# PlusShield.net
KiCad netlist of a schematic drawn in EAGLE
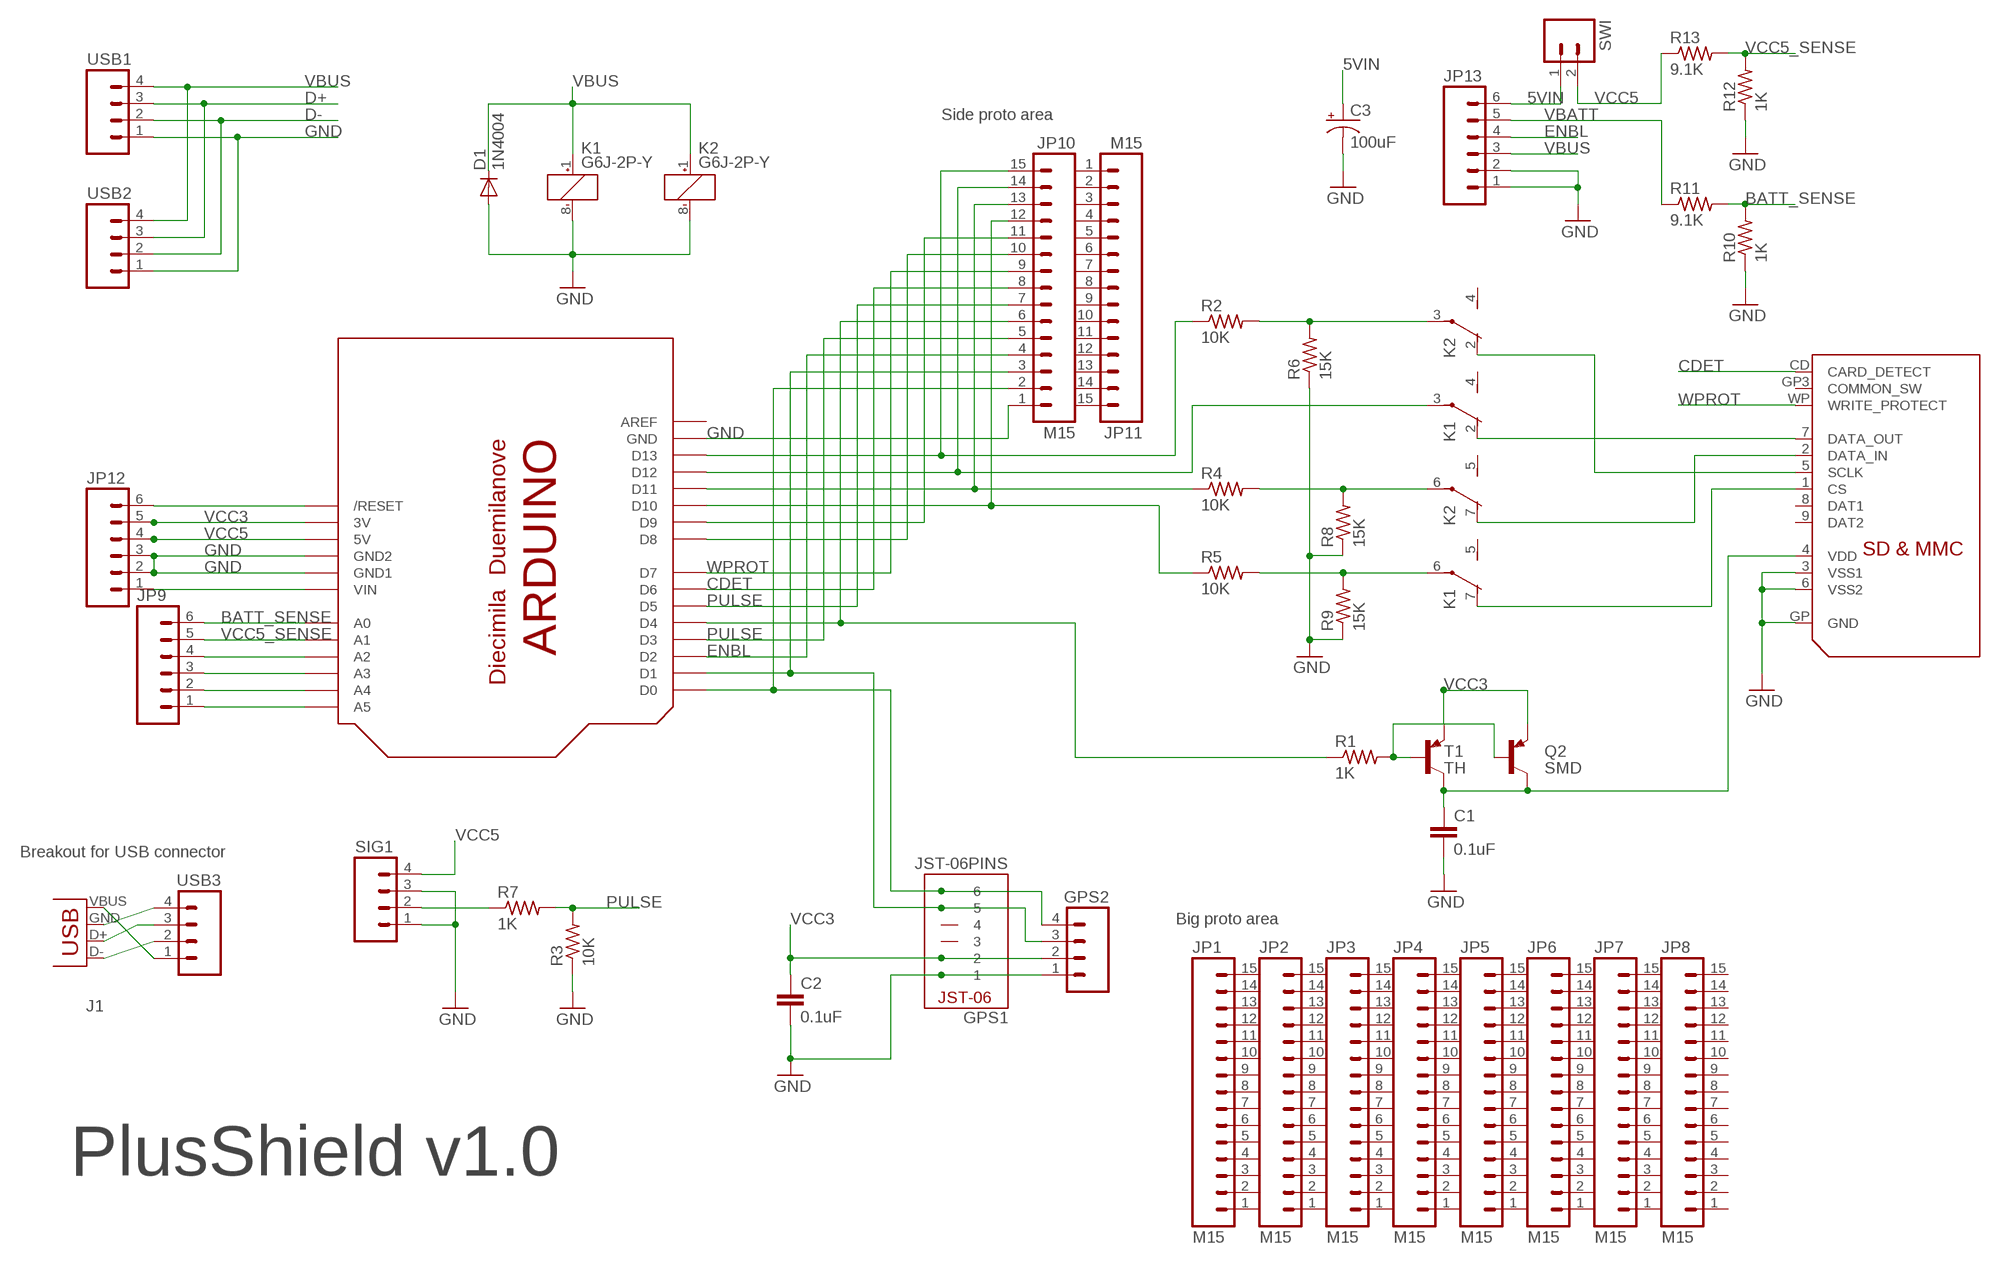
[diagram p0: schematic, sheet 1]

(export (version "E")
  (design (tool "Eeschema 10.0.6"))
  (components
    (comp (ref "C1")
      (value "0.1uF")
      (footprint "eagle-import:CAP-PTH-5MM")
      (libsource (lib "eagle-import") (part "CAPPTH1"))
    )
    (comp (ref "C2")
      (value "0.1uF")
      (footprint "eagle-import:CAP-PTH-5MM")
      (libsource (lib "eagle-import") (part "CAPPTH1"))
    )
    (comp (ref "C3")
      (value "100uF")
      (footprint "eagle-import:EIA7343")
      (libsource (lib "eagle-import") (part "CAP_POL7343"))
    )
    (comp (ref "D1")
      (value "1N4004")
      (footprint "eagle-import:DO41-10")
      (libsource (lib "eagle-import") (part "1N4004"))
    )
    (comp (ref "GPS1")
      (value "JST-06PINS")
      (footprint "eagle-import:JST-SM06B-SRSS-TB")
      (libsource (lib "eagle-import") (part "JST-06PINS"))
    )
    (comp (ref "GPS2")
      (value "M04PTH")
      (footprint "eagle-import:1X04")
      (libsource (lib "eagle-import") (part "M04PTH"))
    )
    (comp (ref "J1")
      (value "USB-A-DIP")
      (footprint "eagle-import:A-DIP")
      (libsource (lib "eagle-import") (part "USB-A-DIP"))
    )
    (comp (ref "JP1")
      (value "M15")
      (footprint "eagle-import:1X15")
      (libsource (lib "eagle-import") (part "M15"))
    )
    (comp (ref "JP2")
      (value "M15")
      (footprint "eagle-import:1X15")
      (libsource (lib "eagle-import") (part "M15"))
    )
    (comp (ref "JP3")
      (value "M15")
      (footprint "eagle-import:1X15")
      (libsource (lib "eagle-import") (part "M15"))
    )
    (comp (ref "JP4")
      (value "M15")
      (footprint "eagle-import:1X15")
      (libsource (lib "eagle-import") (part "M15"))
    )
    (comp (ref "JP5")
      (value "M15")
      (footprint "eagle-import:1X15")
      (libsource (lib "eagle-import") (part "M15"))
    )
    (comp (ref "JP6")
      (value "M15")
      (footprint "eagle-import:1X15")
      (libsource (lib "eagle-import") (part "M15"))
    )
    (comp (ref "JP7")
      (value "M15")
      (footprint "eagle-import:1X15")
      (libsource (lib "eagle-import") (part "M15"))
    )
    (comp (ref "JP8")
      (value "M15")
      (footprint "eagle-import:1X15")
      (libsource (lib "eagle-import") (part "M15"))
    )
    (comp (ref "JP9")
      (value "M06SIP")
      (footprint "eagle-import:1X06")
      (libsource (lib "eagle-import") (part "M06SIP"))
    )
    (comp (ref "JP10")
      (value "M15")
      (footprint "eagle-import:1X15")
      (libsource (lib "eagle-import") (part "M15"))
    )
    (comp (ref "JP11")
      (value "M15")
      (footprint "eagle-import:1X15")
      (libsource (lib "eagle-import") (part "M15"))
    )
    (comp (ref "JP12")
      (value "M06SIP")
      (footprint "eagle-import:1X06")
      (libsource (lib "eagle-import") (part "M06SIP"))
    )
    (comp (ref "JP13")
      (value "M06SIP")
      (footprint "eagle-import:1X06")
      (libsource (lib "eagle-import") (part "M06SIP"))
    )
    (comp (ref "K1")
      (value "G6J-2P-Y")
      (footprint "eagle-import:G6J-2P-Y")
      (fields (field (name "MF") "OMRON COMPONENTS USA") (field (name "MPN") "G6J-2P-Y-DC12"))
      (libsource (lib "eagle-import") (part "G6J-2?-YP"))
    )
    (comp (ref "K2")
      (value "G6J-2P-Y")
      (footprint "eagle-import:G6J-2P-Y")
      (fields (field (name "MF") "OMRON COMPONENTS USA") (field (name "MPN") "G6J-2P-Y-DC12"))
      (libsource (lib "eagle-import") (part "G6J-2?-YP"))
    )
    (comp (ref "Q2")
      (value "SMD")
      (footprint "eagle-import:SOT23")
      (libsource (lib "eagle-import") (part "-?SOT23MMBTA56"))
    )
    (comp (ref "R1")
      (value "1K")
      (footprint "eagle-import:0207_10")
      (libsource (lib "eagle-import") (part "R-US_0207/10"))
    )
    (comp (ref "R2")
      (value "10K")
      (footprint "eagle-import:0207_10")
      (libsource (lib "eagle-import") (part "R-US_0207/10"))
    )
    (comp (ref "R3")
      (value "10K")
      (footprint "eagle-import:0207_10")
      (libsource (lib "eagle-import") (part "R-US_0207/10"))
    )
    (comp (ref "R4")
      (value "10K")
      (footprint "eagle-import:0207_10")
      (libsource (lib "eagle-import") (part "R-US_0207/10"))
    )
    (comp (ref "R5")
      (value "10K")
      (footprint "eagle-import:0207_10")
      (libsource (lib "eagle-import") (part "R-US_0207/10"))
    )
    (comp (ref "R6")
      (value "15K")
      (footprint "eagle-import:0207_10")
      (libsource (lib "eagle-import") (part "R-US_0207/10"))
    )
    (comp (ref "R7")
      (value "1K")
      (footprint "eagle-import:0207_10")
      (libsource (lib "eagle-import") (part "R-US_0207/10"))
    )
    (comp (ref "R8")
      (value "15K")
      (footprint "eagle-import:0207_10")
      (libsource (lib "eagle-import") (part "R-US_0207/10"))
    )
    (comp (ref "R9")
      (value "15K")
      (footprint "eagle-import:0207_10")
      (libsource (lib "eagle-import") (part "R-US_0207/10"))
    )
    (comp (ref "R10")
      (value "1K")
      (footprint "eagle-import:0207_10")
      (libsource (lib "eagle-import") (part "R-US_0207/10"))
    )
    (comp (ref "R11")
      (value "9.1K")
      (footprint "eagle-import:0207_10")
      (libsource (lib "eagle-import") (part "R-US_0207/10"))
    )
    (comp (ref "R12")
      (value "1K")
      (footprint "eagle-import:0207_10")
      (libsource (lib "eagle-import") (part "R-US_0207/10"))
    )
    (comp (ref "R13")
      (value "9.1K")
      (footprint "eagle-import:0207_10")
      (libsource (lib "eagle-import") (part "R-US_0207/10"))
    )
    (comp (ref "SIG1")
      (value "M04PTH")
      (footprint "eagle-import:1X04")
      (libsource (lib "eagle-import") (part "M04PTH"))
    )
    (comp (ref "SWI")
      (value "M02PTH")
      (footprint "eagle-import:1X02")
      (libsource (lib "eagle-import") (part "M02PTH"))
    )
    (comp (ref "T1")
      (value "TH")
      (footprint "eagle-import:TO92-CBE")
      (libsource (lib "eagle-import") (part "-?TO92MPSA56"))
    )
    (comp (ref "U$1")
      (value "SDMMC06132")
      (footprint "eagle-import:06132")
      (libsource (lib "eagle-import") (part "SDMMC06132"))
    )
    (comp (ref "U$2")
      (value "ARDUINOSHIELD-NOHOLE")
      (footprint "eagle-import:ARDUINO-NOHOLE")
      (libsource (lib "eagle-import") (part "ARDUINOSHIELD-NOHOLE"))
    )
    (comp (ref "USB1")
      (value "M04PTH")
      (footprint "eagle-import:1X04")
      (libsource (lib "eagle-import") (part "M04PTH"))
    )
    (comp (ref "USB2")
      (value "M04PTH")
      (footprint "eagle-import:1X04")
      (libsource (lib "eagle-import") (part "M04PTH"))
    )
    (comp (ref "USB3")
      (value "M04PTH")
      (footprint "eagle-import:1X04")
      (libsource (lib "eagle-import") (part "M04PTH"))
    )
  )
  (nets
    (net (code "1") (name "/5VIN") (class "Default")
      (node (ref "C3") (pin "A") (pinfunction "+_A") (pintype "passive"))
      (node (ref "JP13") (pin "6") (pinfunction "6_6") (pintype "passive"))
      (node (ref "SWI") (pin "1") (pinfunction "1_1") (pintype "passive"))
    )
    (net (code "2") (name "/BATT_SENSE") (class "Default")
      (node (ref "JP9") (pin "6") (pinfunction "6_6") (pintype "passive"))
      (node (ref "R10") (pin "2") (pinfunction "2_2") (pintype "passive"))
      (node (ref "R11") (pin "2") (pinfunction "2_2") (pintype "passive"))
      (node (ref "U$2") (pin "A0") (pinfunction "A0_A0") (pintype "bidirectional"))
    )
    (net (code "3") (name "/CDET") (class "Default")
      (node (ref "JP10") (pin "8") (pinfunction "8_8") (pintype "passive"))
      (node (ref "U$1") (pin "CD") (pinfunction "CARD_DETECT_CD") (pintype "passive"))
      (node (ref "U$2") (pin "D6") (pinfunction "D6_D6") (pintype "bidirectional"))
    )
    (net (code "4") (name "/D+") (class "Default")
      (node (ref "USB1") (pin "3") (pinfunction "3_3") (pintype "passive"))
      (node (ref "USB2") (pin "3") (pinfunction "3_3") (pintype "passive"))
    )
    (net (code "5") (name "/D-") (class "Default")
      (node (ref "USB1") (pin "2") (pinfunction "2_2") (pintype "passive"))
      (node (ref "USB2") (pin "2") (pinfunction "2_2") (pintype "passive"))
    )
    (net (code "6") (name "/ENBL") (class "Default")
      (node (ref "JP10") (pin "4") (pinfunction "4_4") (pintype "passive"))
      (node (ref "JP13") (pin "4") (pinfunction "4_4") (pintype "passive"))
      (node (ref "U$2") (pin "D2") (pinfunction "D2_D2") (pintype "bidirectional"))
    )
    (net (code "7") (name "/PULSE") (class "Default")
      (node (ref "JP10") (pin "5") (pinfunction "5_5") (pintype "passive"))
      (node (ref "JP10") (pin "7") (pinfunction "7_7") (pintype "passive"))
      (node (ref "R3") (pin "2") (pinfunction "2_2") (pintype "passive"))
      (node (ref "R7") (pin "2") (pinfunction "2_2") (pintype "passive"))
      (node (ref "U$2") (pin "D3") (pinfunction "D3_D3") (pintype "bidirectional"))
      (node (ref "U$2") (pin "D5") (pinfunction "D5_D5") (pintype "bidirectional"))
    )
    (net (code "8") (name "/VBATT") (class "Default")
      (node (ref "JP13") (pin "5") (pinfunction "5_5") (pintype "passive"))
      (node (ref "R11") (pin "1") (pinfunction "1_1") (pintype "passive"))
    )
    (net (code "9") (name "/VBUS") (class "Default")
      (node (ref "D1") (pin "C") (pinfunction "C_C") (pintype "passive"))
      (node (ref "JP13") (pin "3") (pinfunction "3_3") (pintype "passive"))
      (node (ref "K1") (pin "1") (pinfunction "+_1") (pintype "passive"))
      (node (ref "K2") (pin "1") (pinfunction "+_1") (pintype "passive"))
      (node (ref "USB1") (pin "4") (pinfunction "4_4") (pintype "passive"))
      (node (ref "USB2") (pin "4") (pinfunction "4_4") (pintype "passive"))
    )
    (net (code "10") (name "/VCC3") (class "Default")
      (node (ref "C2") (pin "1") (pinfunction "1_1") (pintype "passive"))
      (node (ref "GPS1") (pin "2") (pinfunction "2_2") (pintype "bidirectional"))
      (node (ref "GPS2") (pin "2") (pinfunction "2_2") (pintype "passive"))
      (node (ref "JP12") (pin "5") (pinfunction "5_5") (pintype "passive"))
      (node (ref "Q2") (pin "2") (pinfunction "E_2") (pintype "passive"))
      (node (ref "T1") (pin "E") (pinfunction "E_E") (pintype "passive"))
      (node (ref "U$2") (pin "3V") (pinfunction "3V_3V") (pintype "power_in"))
    )
    (net (code "11") (name "/VCC5") (class "Default")
      (node (ref "JP12") (pin "4") (pinfunction "4_4") (pintype "passive"))
      (node (ref "R13") (pin "1") (pinfunction "1_1") (pintype "passive"))
      (node (ref "SIG1") (pin "4") (pinfunction "4_4") (pintype "passive"))
      (node (ref "SWI") (pin "2") (pinfunction "2_2") (pintype "passive"))
      (node (ref "U$2") (pin "5V") (pinfunction "5V_5V") (pintype "power_in"))
    )
    (net (code "12") (name "/VCC5_SENSE") (class "Default")
      (node (ref "JP9") (pin "5") (pinfunction "5_5") (pintype "passive"))
      (node (ref "R12") (pin "2") (pinfunction "2_2") (pintype "passive"))
      (node (ref "R13") (pin "2") (pinfunction "2_2") (pintype "passive"))
      (node (ref "U$2") (pin "A1") (pinfunction "A1_A1") (pintype "bidirectional"))
    )
    (net (code "13") (name "/WPROT") (class "Default")
      (node (ref "JP10") (pin "9") (pinfunction "9_9") (pintype "passive"))
      (node (ref "U$1") (pin "WP") (pinfunction "WRITE_PROTECT_WP") (pintype "passive"))
      (node (ref "U$2") (pin "D7") (pinfunction "D7_D7") (pintype "bidirectional"))
    )
    (net (code "14") (name "GND") (class "Default")
      (node (ref "C1") (pin "2") (pinfunction "2_2") (pintype "passive"))
      (node (ref "C2") (pin "2") (pinfunction "2_2") (pintype "passive"))
      (node (ref "C3") (pin "C") (pinfunction "-_C") (pintype "passive"))
      (node (ref "D1") (pin "A") (pinfunction "A_A") (pintype "passive"))
      (node (ref "GPS1") (pin "1") (pinfunction "1_1") (pintype "bidirectional"))
      (node (ref "GPS2") (pin "1") (pinfunction "1_1") (pintype "passive"))
      (node (ref "JP10") (pin "1") (pinfunction "1_1") (pintype "passive"))
      (node (ref "JP12") (pin "2") (pinfunction "2_2") (pintype "passive"))
      (node (ref "JP12") (pin "3") (pinfunction "3_3") (pintype "passive"))
      (node (ref "JP13") (pin "1") (pinfunction "1_1") (pintype "passive"))
      (node (ref "JP13") (pin "2") (pinfunction "2_2") (pintype "passive"))
      (node (ref "K1") (pin "8") (pinfunction "-_8") (pintype "passive"))
      (node (ref "K2") (pin "8") (pinfunction "-_8") (pintype "passive"))
      (node (ref "R10") (pin "1") (pinfunction "1_1") (pintype "passive"))
      (node (ref "R12") (pin "1") (pinfunction "1_1") (pintype "passive"))
      (node (ref "R3") (pin "1") (pinfunction "1_1") (pintype "passive"))
      (node (ref "R6") (pin "1") (pinfunction "1_1") (pintype "passive"))
      (node (ref "R8") (pin "1") (pinfunction "1_1") (pintype "passive"))
      (node (ref "R9") (pin "1") (pinfunction "1_1") (pintype "passive"))
      (node (ref "SIG1") (pin "1") (pinfunction "1_1") (pintype "passive"))
      (node (ref "SIG1") (pin "3") (pinfunction "3_3") (pintype "passive"))
      (node (ref "U$1") (pin "3") (pinfunction "VSS1_3") (pintype "power_in"))
      (node (ref "U$1") (pin "6") (pinfunction "VSS2_6") (pintype "power_in"))
      (node (ref "U$1") (pin "GP") (pinfunction "GND_GP") (pintype "power_in"))
      (node (ref "U$2") (pin "GND") (pinfunction "GND_GND") (pintype "power_in"))
      (node (ref "U$2") (pin "GND1") (pinfunction "GND1_GND1") (pintype "power_in"))
      (node (ref "U$2") (pin "GND2") (pinfunction "GND2_GND2") (pintype "power_in"))
      (node (ref "USB1") (pin "1") (pinfunction "1_1") (pintype "passive"))
      (node (ref "USB2") (pin "1") (pinfunction "1_1") (pintype "passive"))
    )
    (net (code "15") (name "Net-(GPS1-Pad5)") (class "Default")
      (node (ref "GPS1") (pin "5") (pinfunction "5_5") (pintype "bidirectional"))
      (node (ref "GPS2") (pin "3") (pinfunction "3_3") (pintype "passive"))
      (node (ref "JP10") (pin "3") (pinfunction "3_3") (pintype "passive"))
      (node (ref "U$2") (pin "D1") (pinfunction "D1_D1") (pintype "bidirectional"))
    )
    (net (code "16") (name "Net-(GPS1-Pad6)") (class "Default")
      (node (ref "GPS1") (pin "6") (pinfunction "6_6") (pintype "bidirectional"))
      (node (ref "GPS2") (pin "4") (pinfunction "4_4") (pintype "passive"))
      (node (ref "JP10") (pin "2") (pinfunction "2_2") (pintype "passive"))
      (node (ref "U$2") (pin "D0") (pinfunction "D0_D0") (pintype "bidirectional"))
    )
    (net (code "17") (name "Net-(J1-D+)") (class "Default")
      (node (ref "J1") (pin "D-") (pinfunction "D+_D-") (pintype "bidirectional"))
      (node (ref "USB3") (pin "2") (pinfunction "2_2") (pintype "passive"))
    )
    (net (code "18") (name "Net-(J1-D-)") (class "Default")
      (node (ref "J1") (pin "D+") (pinfunction "D-_D+") (pintype "bidirectional"))
      (node (ref "USB3") (pin "3") (pinfunction "3_3") (pintype "passive"))
    )
    (net (code "19") (name "Net-(J1-GND)") (class "Default")
      (node (ref "J1") (pin "VBUS") (pinfunction "GND_VBUS") (pintype "bidirectional"))
      (node (ref "USB3") (pin "1") (pinfunction "1_1") (pintype "passive"))
    )
    (net (code "20") (name "Net-(J1-VBUS)") (class "Default")
      (node (ref "J1") (pin "GND") (pinfunction "VBUS_GND") (pintype "bidirectional"))
      (node (ref "USB3") (pin "4") (pinfunction "4_4") (pintype "passive"))
    )
    (net (code "21") (name "Net-(JP9-Pad1)") (class "Default")
      (node (ref "JP9") (pin "1") (pinfunction "1_1") (pintype "passive"))
      (node (ref "U$2") (pin "A5") (pinfunction "A5_A5") (pintype "bidirectional"))
    )
    (net (code "22") (name "Net-(JP9-Pad2)") (class "Default")
      (node (ref "JP9") (pin "2") (pinfunction "2_2") (pintype "passive"))
      (node (ref "U$2") (pin "A4") (pinfunction "A4_A4") (pintype "bidirectional"))
    )
    (net (code "23") (name "Net-(JP9-Pad3)") (class "Default")
      (node (ref "JP9") (pin "3") (pinfunction "3_3") (pintype "passive"))
      (node (ref "U$2") (pin "A3") (pinfunction "A3_A3") (pintype "bidirectional"))
    )
    (net (code "24") (name "Net-(JP9-Pad4)") (class "Default")
      (node (ref "JP9") (pin "4") (pinfunction "4_4") (pintype "passive"))
      (node (ref "U$2") (pin "A2") (pinfunction "A2_A2") (pintype "bidirectional"))
    )
    (net (code "25") (name "Net-(JP10-Pad6)") (class "Default")
      (node (ref "JP10") (pin "6") (pinfunction "6_6") (pintype "passive"))
      (node (ref "R1") (pin "1") (pinfunction "1_1") (pintype "passive"))
      (node (ref "U$2") (pin "D4") (pinfunction "D4_D4") (pintype "bidirectional"))
    )
    (net (code "26") (name "Net-(JP10-Pad10)") (class "Default")
      (node (ref "JP10") (pin "10") (pinfunction "10_10") (pintype "passive"))
      (node (ref "U$2") (pin "D8") (pinfunction "D8_D8") (pintype "bidirectional"))
    )
    (net (code "27") (name "Net-(JP10-Pad11)") (class "Default")
      (node (ref "JP10") (pin "11") (pinfunction "11_11") (pintype "passive"))
      (node (ref "U$2") (pin "D9") (pinfunction "D9_D9") (pintype "bidirectional"))
    )
    (net (code "28") (name "Net-(JP10-Pad12)") (class "Default")
      (node (ref "JP10") (pin "12") (pinfunction "12_12") (pintype "passive"))
      (node (ref "R5") (pin "1") (pinfunction "1_1") (pintype "passive"))
      (node (ref "U$2") (pin "D10") (pinfunction "D10_D10") (pintype "bidirectional"))
    )
    (net (code "29") (name "Net-(JP10-Pad13)") (class "Default")
      (node (ref "JP10") (pin "13") (pinfunction "13_13") (pintype "passive"))
      (node (ref "R4") (pin "1") (pinfunction "1_1") (pintype "passive"))
      (node (ref "U$2") (pin "D11") (pinfunction "D11_D11") (pintype "bidirectional"))
    )
    (net (code "30") (name "Net-(JP10-Pad15)") (class "Default")
      (node (ref "JP10") (pin "15") (pinfunction "15_15") (pintype "passive"))
      (node (ref "R2") (pin "1") (pinfunction "1_1") (pintype "passive"))
      (node (ref "U$2") (pin "D13") (pinfunction "D13_D13") (pintype "bidirectional"))
    )
    (net (code "31") (name "Net-(JP12-Pad1)") (class "Default")
      (node (ref "JP12") (pin "1") (pinfunction "1_1") (pintype "passive"))
      (node (ref "U$2") (pin "VIN") (pinfunction "VIN_VIN") (pintype "power_in"))
    )
    (net (code "32") (name "Net-(K1B-O)") (class "Default")
      (node (ref "K1") (pin "2") (pinfunction "O_2") (pintype "passive"))
      (node (ref "U$1") (pin "7") (pinfunction "DATA_OUT_7") (pintype "output"))
    )
    (net (code "33") (name "Net-(K1B-P)") (class "Default")
      (node (ref "JP10") (pin "14") (pinfunction "14_14") (pintype "passive"))
      (node (ref "K1") (pin "3") (pinfunction "P_3") (pintype "passive"))
      (node (ref "U$2") (pin "D12") (pinfunction "D12_D12") (pintype "bidirectional"))
    )
    (net (code "34") (name "Net-(K1C-O)") (class "Default")
      (node (ref "K1") (pin "7") (pinfunction "O_7") (pintype "passive"))
      (node (ref "U$1") (pin "1") (pinfunction "CS_1") (pintype "input"))
    )
    (net (code "35") (name "Net-(K1C-P)") (class "Default")
      (node (ref "K1") (pin "6") (pinfunction "P_6") (pintype "passive"))
      (node (ref "R5") (pin "2") (pinfunction "2_2") (pintype "passive"))
      (node (ref "R9") (pin "2") (pinfunction "2_2") (pintype "passive"))
    )
    (net (code "36") (name "Net-(K2B-O)") (class "Default")
      (node (ref "K2") (pin "2") (pinfunction "O_2") (pintype "passive"))
      (node (ref "U$1") (pin "5") (pinfunction "SCLK_5") (pintype "input"))
    )
    (net (code "37") (name "Net-(K2B-P)") (class "Default")
      (node (ref "K2") (pin "3") (pinfunction "P_3") (pintype "passive"))
      (node (ref "R2") (pin "2") (pinfunction "2_2") (pintype "passive"))
      (node (ref "R6") (pin "2") (pinfunction "2_2") (pintype "passive"))
    )
    (net (code "38") (name "Net-(K2C-O)") (class "Default")
      (node (ref "K2") (pin "7") (pinfunction "O_7") (pintype "passive"))
      (node (ref "U$1") (pin "2") (pinfunction "DATA_IN_2") (pintype "input"))
    )
    (net (code "39") (name "Net-(K2C-P)") (class "Default")
      (node (ref "K2") (pin "6") (pinfunction "P_6") (pintype "passive"))
      (node (ref "R4") (pin "2") (pinfunction "2_2") (pintype "passive"))
      (node (ref "R8") (pin "2") (pinfunction "2_2") (pintype "passive"))
    )
    (net (code "40") (name "Net-(Q2-B)") (class "Default")
      (node (ref "Q2") (pin "1") (pinfunction "B_1") (pintype "passive"))
      (node (ref "R1") (pin "2") (pinfunction "2_2") (pintype "passive"))
      (node (ref "T1") (pin "B") (pinfunction "B_B") (pintype "passive"))
    )
    (net (code "41") (name "Net-(Q2-C)") (class "Default")
      (node (ref "C1") (pin "1") (pinfunction "1_1") (pintype "passive"))
      (node (ref "Q2") (pin "3") (pinfunction "C_3") (pintype "passive"))
      (node (ref "T1") (pin "C") (pinfunction "C_C") (pintype "passive"))
      (node (ref "U$1") (pin "4") (pinfunction "VDD_4") (pintype "power_in"))
    )
    (net (code "42") (name "Net-(R7-Pad1)") (class "Default")
      (node (ref "R7") (pin "1") (pinfunction "1_1") (pintype "passive"))
      (node (ref "SIG1") (pin "2") (pinfunction "2_2") (pintype "passive"))
    )
    (net (code "43") (name "Net-(U$2-{slash}RESET)") (class "Default")
      (node (ref "JP12") (pin "6") (pinfunction "6_6") (pintype "passive"))
      (node (ref "U$2") (pin "RESET") (pinfunction "/RESET_RESET") (pintype "bidirectional"))
    )
    (net (code "44") (name "unconnected-(GPS1-Pad3)") (class "Default")
      (node (ref "GPS1") (pin "3") (pinfunction "3_3") (pintype "bidirectional"))
    )
    (net (code "45") (name "unconnected-(GPS1-Pad4)") (class "Default")
      (node (ref "GPS1") (pin "4") (pinfunction "4_4") (pintype "bidirectional"))
    )
    (net (code "46") (name "unconnected-(JP1-Pad1)") (class "Default")
      (node (ref "JP1") (pin "1") (pinfunction "1_1") (pintype "passive"))
    )
    (net (code "47") (name "unconnected-(JP1-Pad2)") (class "Default")
      (node (ref "JP1") (pin "2") (pinfunction "2_2") (pintype "passive"))
    )
    (net (code "48") (name "unconnected-(JP1-Pad3)") (class "Default")
      (node (ref "JP1") (pin "3") (pinfunction "3_3") (pintype "passive"))
    )
    (net (code "49") (name "unconnected-(JP1-Pad4)") (class "Default")
      (node (ref "JP1") (pin "4") (pinfunction "4_4") (pintype "passive"))
    )
    (net (code "50") (name "unconnected-(JP1-Pad5)") (class "Default")
      (node (ref "JP1") (pin "5") (pinfunction "5_5") (pintype "passive"))
    )
    (net (code "51") (name "unconnected-(JP1-Pad6)") (class "Default")
      (node (ref "JP1") (pin "6") (pinfunction "6_6") (pintype "passive"))
    )
    (net (code "52") (name "unconnected-(JP1-Pad7)") (class "Default")
      (node (ref "JP1") (pin "7") (pinfunction "7_7") (pintype "passive"))
    )
    (net (code "53") (name "unconnected-(JP1-Pad8)") (class "Default")
      (node (ref "JP1") (pin "8") (pinfunction "8_8") (pintype "passive"))
    )
    (net (code "54") (name "unconnected-(JP1-Pad9)") (class "Default")
      (node (ref "JP1") (pin "9") (pinfunction "9_9") (pintype "passive"))
    )
    (net (code "55") (name "unconnected-(JP1-Pad10)") (class "Default")
      (node (ref "JP1") (pin "10") (pinfunction "10_10") (pintype "passive"))
    )
    (net (code "56") (name "unconnected-(JP1-Pad11)") (class "Default")
      (node (ref "JP1") (pin "11") (pinfunction "11_11") (pintype "passive"))
    )
    (net (code "57") (name "unconnected-(JP1-Pad12)") (class "Default")
      (node (ref "JP1") (pin "12") (pinfunction "12_12") (pintype "passive"))
    )
    (net (code "58") (name "unconnected-(JP1-Pad13)") (class "Default")
      (node (ref "JP1") (pin "13") (pinfunction "13_13") (pintype "passive"))
    )
    (net (code "59") (name "unconnected-(JP1-Pad14)") (class "Default")
      (node (ref "JP1") (pin "14") (pinfunction "14_14") (pintype "passive"))
    )
    (net (code "60") (name "unconnected-(JP1-Pad15)") (class "Default")
      (node (ref "JP1") (pin "15") (pinfunction "15_15") (pintype "passive"))
    )
    (net (code "61") (name "unconnected-(JP2-Pad1)") (class "Default")
      (node (ref "JP2") (pin "1") (pinfunction "1_1") (pintype "passive"))
    )
    (net (code "62") (name "unconnected-(JP2-Pad2)") (class "Default")
      (node (ref "JP2") (pin "2") (pinfunction "2_2") (pintype "passive"))
    )
    (net (code "63") (name "unconnected-(JP2-Pad3)") (class "Default")
      (node (ref "JP2") (pin "3") (pinfunction "3_3") (pintype "passive"))
    )
    (net (code "64") (name "unconnected-(JP2-Pad4)") (class "Default")
      (node (ref "JP2") (pin "4") (pinfunction "4_4") (pintype "passive"))
    )
    (net (code "65") (name "unconnected-(JP2-Pad5)") (class "Default")
      (node (ref "JP2") (pin "5") (pinfunction "5_5") (pintype "passive"))
    )
    (net (code "66") (name "unconnected-(JP2-Pad6)") (class "Default")
      (node (ref "JP2") (pin "6") (pinfunction "6_6") (pintype "passive"))
    )
    (net (code "67") (name "unconnected-(JP2-Pad7)") (class "Default")
      (node (ref "JP2") (pin "7") (pinfunction "7_7") (pintype "passive"))
    )
    (net (code "68") (name "unconnected-(JP2-Pad8)") (class "Default")
      (node (ref "JP2") (pin "8") (pinfunction "8_8") (pintype "passive"))
    )
    (net (code "69") (name "unconnected-(JP2-Pad9)") (class "Default")
      (node (ref "JP2") (pin "9") (pinfunction "9_9") (pintype "passive"))
    )
    (net (code "70") (name "unconnected-(JP2-Pad10)") (class "Default")
      (node (ref "JP2") (pin "10") (pinfunction "10_10") (pintype "passive"))
    )
    (net (code "71") (name "unconnected-(JP2-Pad11)") (class "Default")
      (node (ref "JP2") (pin "11") (pinfunction "11_11") (pintype "passive"))
    )
    (net (code "72") (name "unconnected-(JP2-Pad12)") (class "Default")
      (node (ref "JP2") (pin "12") (pinfunction "12_12") (pintype "passive"))
    )
    (net (code "73") (name "unconnected-(JP2-Pad13)") (class "Default")
      (node (ref "JP2") (pin "13") (pinfunction "13_13") (pintype "passive"))
    )
    (net (code "74") (name "unconnected-(JP2-Pad14)") (class "Default")
      (node (ref "JP2") (pin "14") (pinfunction "14_14") (pintype "passive"))
    )
    (net (code "75") (name "unconnected-(JP2-Pad15)") (class "Default")
      (node (ref "JP2") (pin "15") (pinfunction "15_15") (pintype "passive"))
    )
    (net (code "76") (name "unconnected-(JP3-Pad1)") (class "Default")
      (node (ref "JP3") (pin "1") (pinfunction "1_1") (pintype "passive"))
    )
    (net (code "77") (name "unconnected-(JP3-Pad2)") (class "Default")
      (node (ref "JP3") (pin "2") (pinfunction "2_2") (pintype "passive"))
    )
    (net (code "78") (name "unconnected-(JP3-Pad3)") (class "Default")
      (node (ref "JP3") (pin "3") (pinfunction "3_3") (pintype "passive"))
    )
    (net (code "79") (name "unconnected-(JP3-Pad4)") (class "Default")
      (node (ref "JP3") (pin "4") (pinfunction "4_4") (pintype "passive"))
    )
    (net (code "80") (name "unconnected-(JP3-Pad5)") (class "Default")
      (node (ref "JP3") (pin "5") (pinfunction "5_5") (pintype "passive"))
    )
    (net (code "81") (name "unconnected-(JP3-Pad6)") (class "Default")
      (node (ref "JP3") (pin "6") (pinfunction "6_6") (pintype "passive"))
    )
    (net (code "82") (name "unconnected-(JP3-Pad7)") (class "Default")
      (node (ref "JP3") (pin "7") (pinfunction "7_7") (pintype "passive"))
    )
    (net (code "83") (name "unconnected-(JP3-Pad8)") (class "Default")
      (node (ref "JP3") (pin "8") (pinfunction "8_8") (pintype "passive"))
    )
    (net (code "84") (name "unconnected-(JP3-Pad9)") (class "Default")
      (node (ref "JP3") (pin "9") (pinfunction "9_9") (pintype "passive"))
    )
    (net (code "85") (name "unconnected-(JP3-Pad10)") (class "Default")
      (node (ref "JP3") (pin "10") (pinfunction "10_10") (pintype "passive"))
    )
    (net (code "86") (name "unconnected-(JP3-Pad11)") (class "Default")
      (node (ref "JP3") (pin "11") (pinfunction "11_11") (pintype "passive"))
    )
    (net (code "87") (name "unconnected-(JP3-Pad12)") (class "Default")
      (node (ref "JP3") (pin "12") (pinfunction "12_12") (pintype "passive"))
    )
    (net (code "88") (name "unconnected-(JP3-Pad13)") (class "Default")
      (node (ref "JP3") (pin "13") (pinfunction "13_13") (pintype "passive"))
    )
    (net (code "89") (name "unconnected-(JP3-Pad14)") (class "Default")
      (node (ref "JP3") (pin "14") (pinfunction "14_14") (pintype "passive"))
    )
    (net (code "90") (name "unconnected-(JP3-Pad15)") (class "Default")
      (node (ref "JP3") (pin "15") (pinfunction "15_15") (pintype "passive"))
    )
    (net (code "91") (name "unconnected-(JP4-Pad1)") (class "Default")
      (node (ref "JP4") (pin "1") (pinfunction "1_1") (pintype "passive"))
    )
    (net (code "92") (name "unconnected-(JP4-Pad2)") (class "Default")
      (node (ref "JP4") (pin "2") (pinfunction "2_2") (pintype "passive"))
    )
    (net (code "93") (name "unconnected-(JP4-Pad3)") (class "Default")
      (node (ref "JP4") (pin "3") (pinfunction "3_3") (pintype "passive"))
    )
    (net (code "94") (name "unconnected-(JP4-Pad4)") (class "Default")
      (node (ref "JP4") (pin "4") (pinfunction "4_4") (pintype "passive"))
    )
    (net (code "95") (name "unconnected-(JP4-Pad5)") (class "Default")
      (node (ref "JP4") (pin "5") (pinfunction "5_5") (pintype "passive"))
    )
    (net (code "96") (name "unconnected-(JP4-Pad6)") (class "Default")
      (node (ref "JP4") (pin "6") (pinfunction "6_6") (pintype "passive"))
    )
    (net (code "97") (name "unconnected-(JP4-Pad7)") (class "Default")
      (node (ref "JP4") (pin "7") (pinfunction "7_7") (pintype "passive"))
    )
    (net (code "98") (name "unconnected-(JP4-Pad8)") (class "Default")
      (node (ref "JP4") (pin "8") (pinfunction "8_8") (pintype "passive"))
    )
    (net (code "99") (name "unconnected-(JP4-Pad9)") (class "Default")
      (node (ref "JP4") (pin "9") (pinfunction "9_9") (pintype "passive"))
    )
    (net (code "100") (name "unconnected-(JP4-Pad10)") (class "Default")
      (node (ref "JP4") (pin "10") (pinfunction "10_10") (pintype "passive"))
    )
    (net (code "101") (name "unconnected-(JP4-Pad11)") (class "Default")
      (node (ref "JP4") (pin "11") (pinfunction "11_11") (pintype "passive"))
    )
    (net (code "102") (name "unconnected-(JP4-Pad12)") (class "Default")
      (node (ref "JP4") (pin "12") (pinfunction "12_12") (pintype "passive"))
    )
    (net (code "103") (name "unconnected-(JP4-Pad13)") (class "Default")
      (node (ref "JP4") (pin "13") (pinfunction "13_13") (pintype "passive"))
    )
    (net (code "104") (name "unconnected-(JP4-Pad14)") (class "Default")
      (node (ref "JP4") (pin "14") (pinfunction "14_14") (pintype "passive"))
    )
    (net (code "105") (name "unconnected-(JP4-Pad15)") (class "Default")
      (node (ref "JP4") (pin "15") (pinfunction "15_15") (pintype "passive"))
    )
    (net (code "106") (name "unconnected-(JP5-Pad1)") (class "Default")
      (node (ref "JP5") (pin "1") (pinfunction "1_1") (pintype "passive"))
    )
    (net (code "107") (name "unconnected-(JP5-Pad2)") (class "Default")
      (node (ref "JP5") (pin "2") (pinfunction "2_2") (pintype "passive"))
    )
    (net (code "108") (name "unconnected-(JP5-Pad3)") (class "Default")
      (node (ref "JP5") (pin "3") (pinfunction "3_3") (pintype "passive"))
    )
    (net (code "109") (name "unconnected-(JP5-Pad4)") (class "Default")
      (node (ref "JP5") (pin "4") (pinfunction "4_4") (pintype "passive"))
    )
    (net (code "110") (name "unconnected-(JP5-Pad5)") (class "Default")
      (node (ref "JP5") (pin "5") (pinfunction "5_5") (pintype "passive"))
    )
    (net (code "111") (name "unconnected-(JP5-Pad6)") (class "Default")
      (node (ref "JP5") (pin "6") (pinfunction "6_6") (pintype "passive"))
    )
    (net (code "112") (name "unconnected-(JP5-Pad7)") (class "Default")
      (node (ref "JP5") (pin "7") (pinfunction "7_7") (pintype "passive"))
    )
    (net (code "113") (name "unconnected-(JP5-Pad8)") (class "Default")
      (node (ref "JP5") (pin "8") (pinfunction "8_8") (pintype "passive"))
    )
    (net (code "114") (name "unconnected-(JP5-Pad9)") (class "Default")
      (node (ref "JP5") (pin "9") (pinfunction "9_9") (pintype "passive"))
    )
    (net (code "115") (name "unconnected-(JP5-Pad10)") (class "Default")
      (node (ref "JP5") (pin "10") (pinfunction "10_10") (pintype "passive"))
    )
    (net (code "116") (name "unconnected-(JP5-Pad11)") (class "Default")
      (node (ref "JP5") (pin "11") (pinfunction "11_11") (pintype "passive"))
    )
    (net (code "117") (name "unconnected-(JP5-Pad12)") (class "Default")
      (node (ref "JP5") (pin "12") (pinfunction "12_12") (pintype "passive"))
    )
    (net (code "118") (name "unconnected-(JP5-Pad13)") (class "Default")
      (node (ref "JP5") (pin "13") (pinfunction "13_13") (pintype "passive"))
    )
    (net (code "119") (name "unconnected-(JP5-Pad14)") (class "Default")
      (node (ref "JP5") (pin "14") (pinfunction "14_14") (pintype "passive"))
    )
    (net (code "120") (name "unconnected-(JP5-Pad15)") (class "Default")
      (node (ref "JP5") (pin "15") (pinfunction "15_15") (pintype "passive"))
    )
    (net (code "121") (name "unconnected-(JP6-Pad1)") (class "Default")
      (node (ref "JP6") (pin "1") (pinfunction "1_1") (pintype "passive"))
    )
    (net (code "122") (name "unconnected-(JP6-Pad2)") (class "Default")
      (node (ref "JP6") (pin "2") (pinfunction "2_2") (pintype "passive"))
    )
    (net (code "123") (name "unconnected-(JP6-Pad3)") (class "Default")
      (node (ref "JP6") (pin "3") (pinfunction "3_3") (pintype "passive"))
    )
    (net (code "124") (name "unconnected-(JP6-Pad4)") (class "Default")
      (node (ref "JP6") (pin "4") (pinfunction "4_4") (pintype "passive"))
    )
    (net (code "125") (name "unconnected-(JP6-Pad5)") (class "Default")
      (node (ref "JP6") (pin "5") (pinfunction "5_5") (pintype "passive"))
    )
    (net (code "126") (name "unconnected-(JP6-Pad6)") (class "Default")
      (node (ref "JP6") (pin "6") (pinfunction "6_6") (pintype "passive"))
    )
    (net (code "127") (name "unconnected-(JP6-Pad7)") (class "Default")
      (node (ref "JP6") (pin "7") (pinfunction "7_7") (pintype "passive"))
    )
    (net (code "128") (name "unconnected-(JP6-Pad8)") (class "Default")
      (node (ref "JP6") (pin "8") (pinfunction "8_8") (pintype "passive"))
    )
    (net (code "129") (name "unconnected-(JP6-Pad9)") (class "Default")
      (node (ref "JP6") (pin "9") (pinfunction "9_9") (pintype "passive"))
    )
    (net (code "130") (name "unconnected-(JP6-Pad10)") (class "Default")
      (node (ref "JP6") (pin "10") (pinfunction "10_10") (pintype "passive"))
    )
    (net (code "131") (name "unconnected-(JP6-Pad11)") (class "Default")
      (node (ref "JP6") (pin "11") (pinfunction "11_11") (pintype "passive"))
    )
    (net (code "132") (name "unconnected-(JP6-Pad12)") (class "Default")
      (node (ref "JP6") (pin "12") (pinfunction "12_12") (pintype "passive"))
    )
    (net (code "133") (name "unconnected-(JP6-Pad13)") (class "Default")
      (node (ref "JP6") (pin "13") (pinfunction "13_13") (pintype "passive"))
    )
    (net (code "134") (name "unconnected-(JP6-Pad14)") (class "Default")
      (node (ref "JP6") (pin "14") (pinfunction "14_14") (pintype "passive"))
    )
    (net (code "135") (name "unconnected-(JP6-Pad15)") (class "Default")
      (node (ref "JP6") (pin "15") (pinfunction "15_15") (pintype "passive"))
    )
    (net (code "136") (name "unconnected-(JP7-Pad1)") (class "Default")
      (node (ref "JP7") (pin "1") (pinfunction "1_1") (pintype "passive"))
    )
    (net (code "137") (name "unconnected-(JP7-Pad2)") (class "Default")
      (node (ref "JP7") (pin "2") (pinfunction "2_2") (pintype "passive"))
    )
    (net (code "138") (name "unconnected-(JP7-Pad3)") (class "Default")
      (node (ref "JP7") (pin "3") (pinfunction "3_3") (pintype "passive"))
    )
    (net (code "139") (name "unconnected-(JP7-Pad4)") (class "Default")
      (node (ref "JP7") (pin "4") (pinfunction "4_4") (pintype "passive"))
    )
    (net (code "140") (name "unconnected-(JP7-Pad5)") (class "Default")
      (node (ref "JP7") (pin "5") (pinfunction "5_5") (pintype "passive"))
    )
    (net (code "141") (name "unconnected-(JP7-Pad6)") (class "Default")
      (node (ref "JP7") (pin "6") (pinfunction "6_6") (pintype "passive"))
    )
    (net (code "142") (name "unconnected-(JP7-Pad7)") (class "Default")
      (node (ref "JP7") (pin "7") (pinfunction "7_7") (pintype "passive"))
    )
    (net (code "143") (name "unconnected-(JP7-Pad8)") (class "Default")
      (node (ref "JP7") (pin "8") (pinfunction "8_8") (pintype "passive"))
    )
    (net (code "144") (name "unconnected-(JP7-Pad9)") (class "Default")
      (node (ref "JP7") (pin "9") (pinfunction "9_9") (pintype "passive"))
    )
    (net (code "145") (name "unconnected-(JP7-Pad10)") (class "Default")
      (node (ref "JP7") (pin "10") (pinfunction "10_10") (pintype "passive"))
    )
    (net (code "146") (name "unconnected-(JP7-Pad11)") (class "Default")
      (node (ref "JP7") (pin "11") (pinfunction "11_11") (pintype "passive"))
    )
    (net (code "147") (name "unconnected-(JP7-Pad12)") (class "Default")
      (node (ref "JP7") (pin "12") (pinfunction "12_12") (pintype "passive"))
    )
    (net (code "148") (name "unconnected-(JP7-Pad13)") (class "Default")
      (node (ref "JP7") (pin "13") (pinfunction "13_13") (pintype "passive"))
    )
    (net (code "149") (name "unconnected-(JP7-Pad14)") (class "Default")
      (node (ref "JP7") (pin "14") (pinfunction "14_14") (pintype "passive"))
    )
    (net (code "150") (name "unconnected-(JP7-Pad15)") (class "Default")
      (node (ref "JP7") (pin "15") (pinfunction "15_15") (pintype "passive"))
    )
    (net (code "151") (name "unconnected-(JP8-Pad1)") (class "Default")
      (node (ref "JP8") (pin "1") (pinfunction "1_1") (pintype "passive"))
    )
    (net (code "152") (name "unconnected-(JP8-Pad2)") (class "Default")
      (node (ref "JP8") (pin "2") (pinfunction "2_2") (pintype "passive"))
    )
    (net (code "153") (name "unconnected-(JP8-Pad3)") (class "Default")
      (node (ref "JP8") (pin "3") (pinfunction "3_3") (pintype "passive"))
    )
    (net (code "154") (name "unconnected-(JP8-Pad4)") (class "Default")
      (node (ref "JP8") (pin "4") (pinfunction "4_4") (pintype "passive"))
    )
    (net (code "155") (name "unconnected-(JP8-Pad5)") (class "Default")
      (node (ref "JP8") (pin "5") (pinfunction "5_5") (pintype "passive"))
    )
    (net (code "156") (name "unconnected-(JP8-Pad6)") (class "Default")
      (node (ref "JP8") (pin "6") (pinfunction "6_6") (pintype "passive"))
    )
    (net (code "157") (name "unconnected-(JP8-Pad7)") (class "Default")
      (node (ref "JP8") (pin "7") (pinfunction "7_7") (pintype "passive"))
    )
    (net (code "158") (name "unconnected-(JP8-Pad8)") (class "Default")
      (node (ref "JP8") (pin "8") (pinfunction "8_8") (pintype "passive"))
    )
    (net (code "159") (name "unconnected-(JP8-Pad9)") (class "Default")
      (node (ref "JP8") (pin "9") (pinfunction "9_9") (pintype "passive"))
    )
    (net (code "160") (name "unconnected-(JP8-Pad10)") (class "Default")
      (node (ref "JP8") (pin "10") (pinfunction "10_10") (pintype "passive"))
    )
    (net (code "161") (name "unconnected-(JP8-Pad11)") (class "Default")
      (node (ref "JP8") (pin "11") (pinfunction "11_11") (pintype "passive"))
    )
    (net (code "162") (name "unconnected-(JP8-Pad12)") (class "Default")
      (node (ref "JP8") (pin "12") (pinfunction "12_12") (pintype "passive"))
    )
    (net (code "163") (name "unconnected-(JP8-Pad13)") (class "Default")
      (node (ref "JP8") (pin "13") (pinfunction "13_13") (pintype "passive"))
    )
    (net (code "164") (name "unconnected-(JP8-Pad14)") (class "Default")
      (node (ref "JP8") (pin "14") (pinfunction "14_14") (pintype "passive"))
    )
    (net (code "165") (name "unconnected-(JP8-Pad15)") (class "Default")
      (node (ref "JP8") (pin "15") (pinfunction "15_15") (pintype "passive"))
    )
    (net (code "166") (name "unconnected-(JP11-Pad1)") (class "Default")
      (node (ref "JP11") (pin "1") (pinfunction "1_1") (pintype "passive"))
    )
    (net (code "167") (name "unconnected-(JP11-Pad2)") (class "Default")
      (node (ref "JP11") (pin "2") (pinfunction "2_2") (pintype "passive"))
    )
    (net (code "168") (name "unconnected-(JP11-Pad3)") (class "Default")
      (node (ref "JP11") (pin "3") (pinfunction "3_3") (pintype "passive"))
    )
    (net (code "169") (name "unconnected-(JP11-Pad4)") (class "Default")
      (node (ref "JP11") (pin "4") (pinfunction "4_4") (pintype "passive"))
    )
    (net (code "170") (name "unconnected-(JP11-Pad5)") (class "Default")
      (node (ref "JP11") (pin "5") (pinfunction "5_5") (pintype "passive"))
    )
    (net (code "171") (name "unconnected-(JP11-Pad6)") (class "Default")
      (node (ref "JP11") (pin "6") (pinfunction "6_6") (pintype "passive"))
    )
    (net (code "172") (name "unconnected-(JP11-Pad7)") (class "Default")
      (node (ref "JP11") (pin "7") (pinfunction "7_7") (pintype "passive"))
    )
    (net (code "173") (name "unconnected-(JP11-Pad8)") (class "Default")
      (node (ref "JP11") (pin "8") (pinfunction "8_8") (pintype "passive"))
    )
    (net (code "174") (name "unconnected-(JP11-Pad9)") (class "Default")
      (node (ref "JP11") (pin "9") (pinfunction "9_9") (pintype "passive"))
    )
    (net (code "175") (name "unconnected-(JP11-Pad10)") (class "Default")
      (node (ref "JP11") (pin "10") (pinfunction "10_10") (pintype "passive"))
    )
    (net (code "176") (name "unconnected-(JP11-Pad11)") (class "Default")
      (node (ref "JP11") (pin "11") (pinfunction "11_11") (pintype "passive"))
    )
    (net (code "177") (name "unconnected-(JP11-Pad12)") (class "Default")
      (node (ref "JP11") (pin "12") (pinfunction "12_12") (pintype "passive"))
    )
    (net (code "178") (name "unconnected-(JP11-Pad13)") (class "Default")
      (node (ref "JP11") (pin "13") (pinfunction "13_13") (pintype "passive"))
    )
    (net (code "179") (name "unconnected-(JP11-Pad14)") (class "Default")
      (node (ref "JP11") (pin "14") (pinfunction "14_14") (pintype "passive"))
    )
    (net (code "180") (name "unconnected-(JP11-Pad15)") (class "Default")
      (node (ref "JP11") (pin "15") (pinfunction "15_15") (pintype "passive"))
    )
    (net (code "181") (name "unconnected-(K1B-S-Pad4)") (class "Default")
      (node (ref "K1") (pin "4") (pinfunction "S_4") (pintype "passive"))
    )
    (net (code "182") (name "unconnected-(K1C-S-Pad5)") (class "Default")
      (node (ref "K1") (pin "5") (pinfunction "S_5") (pintype "passive"))
    )
    (net (code "183") (name "unconnected-(K2B-S-Pad4)") (class "Default")
      (node (ref "K2") (pin "4") (pinfunction "S_4") (pintype "passive"))
    )
    (net (code "184") (name "unconnected-(K2C-S-Pad5)") (class "Default")
      (node (ref "K2") (pin "5") (pinfunction "S_5") (pintype "passive"))
    )
    (net (code "185") (name "unconnected-(U$1-COMMON_SW-PadGP3)") (class "Default")
      (node (ref "U$1") (pin "GP3") (pinfunction "COMMON_SW_GP3") (pintype "passive"))
    )
    (net (code "186") (name "unconnected-(U$1-DAT1-Pad8)") (class "Default")
      (node (ref "U$1") (pin "8") (pinfunction "DAT1_8") (pintype "bidirectional"))
    )
    (net (code "187") (name "unconnected-(U$1-DAT2-Pad9)") (class "Default")
      (node (ref "U$1") (pin "9") (pinfunction "DAT2_9") (pintype "bidirectional"))
    )
    (net (code "188") (name "unconnected-(U$2-PadAREF)") (class "Default")
      (node (ref "U$2") (pin "AREF") (pinfunction "AREF_AREF") (pintype "bidirectional"))
    )
  )
)
